# HX6320_SchDoc.net
KiCad netlist of a schematic drawn in Altium Designer
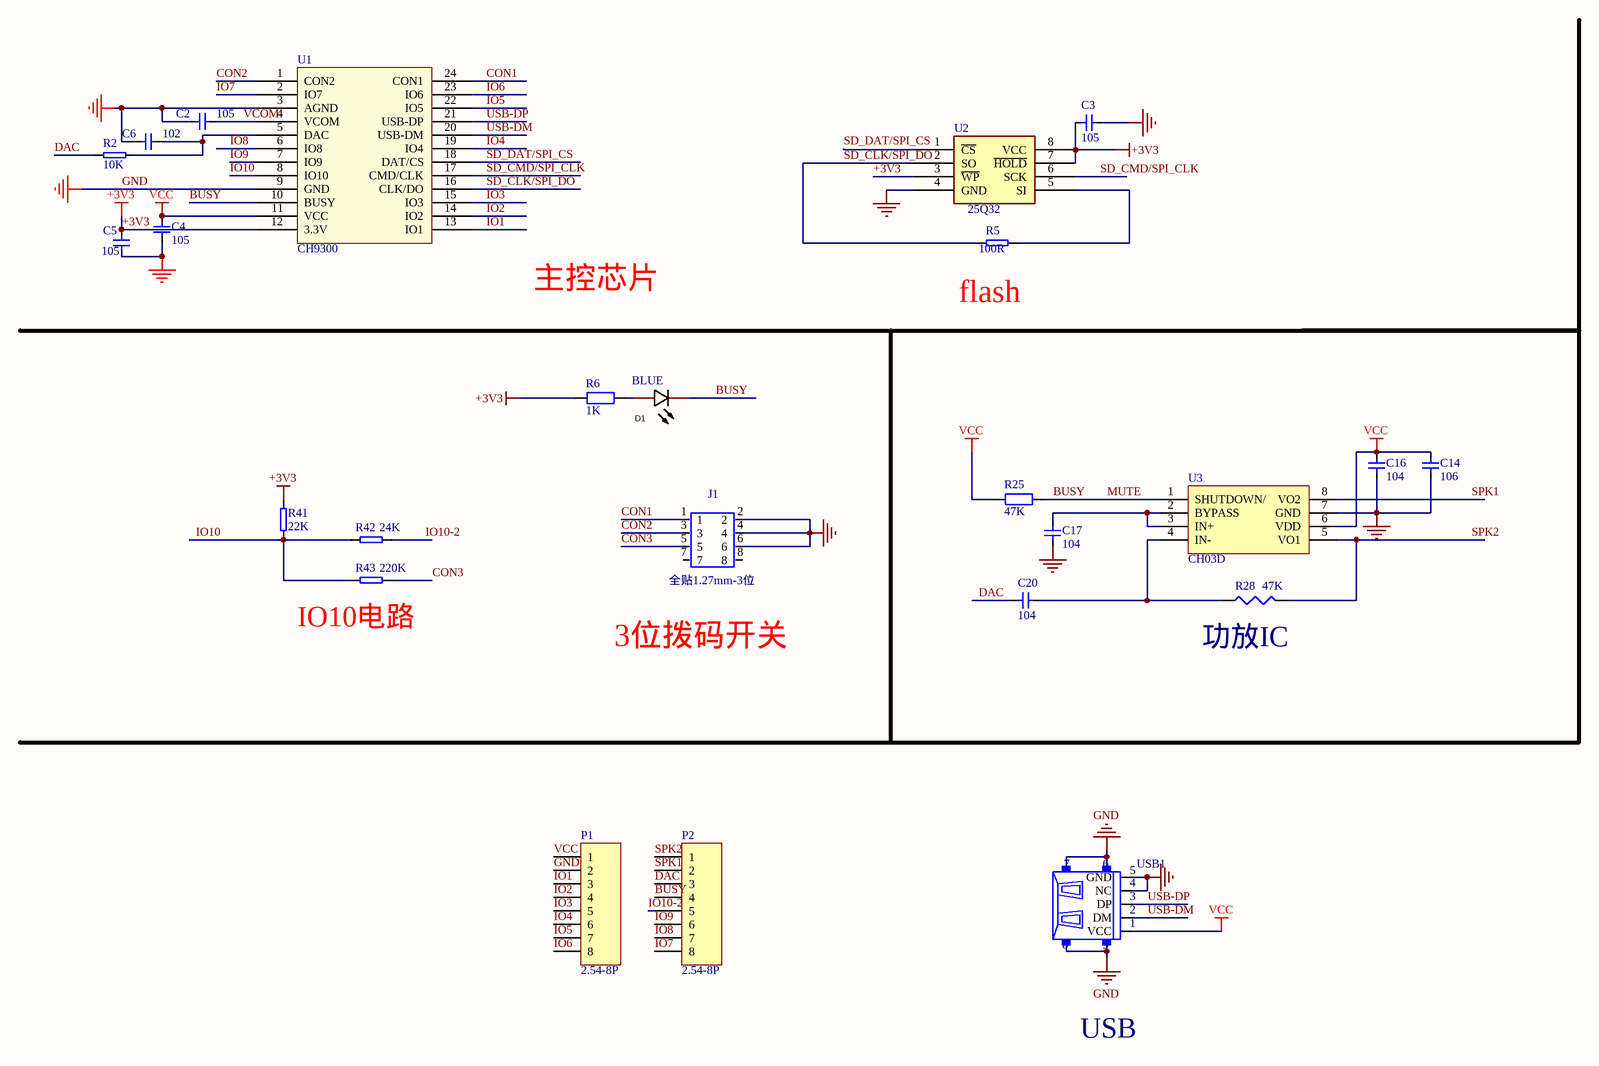
[diagram p0: HX6320.SchDoc.schdoc]

(export (version "E")
  (design (tool "Eeschema 10.0.6"))
  (components
    (comp (ref "C2")
      (value "105")
      (footprint "C0603")
      (description "Capacitor")
      (libsource (lib "*") (part "CAP"))
    )
    (comp (ref "C3")
      (value "105")
      (footprint "C0603")
      (description "Capacitor")
      (libsource (lib "*") (part "CAP"))
    )
    (comp (ref "C4")
      (value "105")
      (footprint "C0603")
      (description "Capacitor")
      (libsource (lib "*") (part "CAP"))
    )
    (comp (ref "C5")
      (value "105")
      (footprint "C0603")
      (description "Capacitor")
      (libsource (lib "*") (part "CAP"))
    )
    (comp (ref "C6")
      (value "102")
      (footprint "C0603")
      (description "Capacitor")
      (libsource (lib "*") (part "CAP"))
    )
    (comp (ref "C14")
      (value "106")
      (footprint "C0603")
      (description "Capacitor")
      (libsource (lib "*") (part "CAP"))
    )
    (comp (ref "C16")
      (value "104")
      (footprint "C0603")
      (description "Capacitor")
      (libsource (lib "*") (part "CAP"))
    )
    (comp (ref "C17")
      (value "104")
      (footprint "C0603")
      (description "Capacitor")
      (libsource (lib "*") (part "CAP"))
    )
    (comp (ref "C20")
      (value "104")
      (footprint "C0603")
      (description "Capacitor")
      (libsource (lib "*") (part "CAP"))
    )
    (comp (ref "D1")
      (value "BLUE")
      (footprint "LC-0603_LED_S1")
      (fields (field (name "MANUFACTURER") "国星光电") (field (name "MANUFACTURER PART") "NCD0603R1"))
      (libsource (lib "altium-import") (part "root_2_NCD0603R1_C84263_"))
    )
    (comp (ref "J1")
      (value "全贴1.27mm-3位")
      (footprint "SW-SMD_DSHP02TSGER")
      (libsource (lib "*") (part "CON_A"))
    )
    (comp (ref "P1")
      (value "2.54-8P")
      (footprint "HDR1X8")
      (description "Header, 8-Pin")
      (fields (field (name "PUBLISHER") "Altium Limited"))
      (libsource (lib "Miscellaneous Connectors") (part "Header 8"))
    )
    (comp (ref "P2")
      (value "2.54-8P")
      (footprint "HDR1X8")
      (description "Header, 8-Pin")
      (fields (field (name "PUBLISHER") "Altium Limited"))
      (libsource (lib "Miscellaneous Connectors") (part "Header 8"))
    )
    (comp (ref "R2") (value "10K") (footprint "R0603") (libsource (lib "*") (part "RES")))
    (comp (ref "R5") (value "100R") (footprint "R0603") (libsource (lib "*") (part "RES")))
    (comp (ref "R6")
      (value "1K")
      (footprint "R0603")
      (description "贴片电阻")
      (fields (field (name "版权归属") "源创客"))
      (libsource (lib "电阻-电容-电感") (part "R"))
    )
    (comp (ref "R25")
      (value "47K")
      (footprint "R0603")
      (description "贴片电阻")
      (fields (field (name "版权归属") "源创客"))
      (libsource (lib "电阻-电容-电感") (part "R"))
    )
    (comp (ref "R28")
      (value "47K")
      (footprint "R0603")
      (description "0805.PcbLib")
      (fields (field (name "PUBLISHER") "Altium Limited"))
      (libsource (lib "*") (part "Res3"))
    )
    (comp (ref "R41") (value "22K") (footprint "R0603") (libsource (lib "*") (part "RES")))
    (comp (ref "R42") (value "24K") (footprint "R0603") (libsource (lib "*") (part "RES")))
    (comp (ref "R43") (value "220K") (footprint "R0603") (libsource (lib "*") (part "RES")))
    (comp (ref "U1") (value "CH9300") (footprint "QSOP24") (libsource (lib "JQ8900") (part "COMPONENT_2")))
    (comp (ref "U2") (value "25Q32") (footprint "LC-SOIC-8_150-208mil") (libsource (lib "*") (part "A25Q32")))
    (comp (ref "U3") (value "CH03D") (footprint "LC-SOP-8_150mil") (libsource (lib "IC") (part "LM4890")))
    (comp (ref "USB1") (value "USB-5PIN") (footprint "USB-MIRO") (libsource (lib "*") (part "USB-5PIN")))
  )
  (nets
    (net (code "1") (name "+3V3") (class "Default")
      (node (ref "C3") (pin "1") (pinfunction "1_1") (pintype "passive"))
      (node (ref "C5") (pin "1") (pinfunction "1_1") (pintype "passive"))
      (node (ref "R41") (pin "2") (pinfunction "2_2") (pintype "passive"))
      (node (ref "R6") (pin "1") (pinfunction "1_1") (pintype "passive"))
      (node (ref "U1") (pin "12") (pinfunction "3.3V_12") (pintype "passive"))
      (node (ref "U2") (pin "3") (pinfunction "~{WP}_3") (pintype "passive"))
      (node (ref "U2") (pin "7") (pinfunction "~{HOLD}_7") (pintype "passive"))
      (node (ref "U2") (pin "8") (pinfunction "VCC_8") (pintype "passive"))
    )
    (net (code "2") (name "/BUSY") (class "Default")
      (node (ref "D1") (pin "1") (pinfunction "K_1") (pintype "passive"))
      (node (ref "P2") (pin "4") (pinfunction "4_4") (pintype "passive"))
      (node (ref "R25") (pin "1") (pinfunction "1_1") (pintype "passive"))
      (node (ref "U1") (pin "10") (pinfunction "BUSY_10") (pintype "passive"))
      (node (ref "U3") (pin "1") (pinfunction "SHUTDOWN/_1") (pintype "passive"))
    )
    (net (code "3") (name "/CON1") (class "Default")
      (node (ref "J1") (pin "1") (pinfunction "1_1") (pintype "passive"))
      (node (ref "U1") (pin "24") (pinfunction "CON1_24") (pintype "passive"))
    )
    (net (code "4") (name "/CON2") (class "Default")
      (node (ref "J1") (pin "3") (pinfunction "3_3") (pintype "passive"))
      (node (ref "U1") (pin "1") (pinfunction "CON2_1") (pintype "passive"))
    )
    (net (code "5") (name "/CON3") (class "Default")
      (node (ref "J1") (pin "5") (pinfunction "5_5") (pintype "passive"))
      (node (ref "R43") (pin "1") (pinfunction "1_1") (pintype "passive"))
    )
    (net (code "6") (name "/DAC") (class "Default")
      (node (ref "C20") (pin "1") (pinfunction "1_1") (pintype "passive"))
      (node (ref "P2") (pin "3") (pinfunction "3_3") (pintype "passive"))
      (node (ref "R2") (pin "2") (pinfunction "2_2") (pintype "passive"))
    )
    (net (code "7") (name "/IO1") (class "Default")
      (node (ref "P1") (pin "3") (pinfunction "3_3") (pintype "passive"))
      (node (ref "U1") (pin "13") (pinfunction "IO1_13") (pintype "passive"))
    )
    (net (code "8") (name "/IO2") (class "Default")
      (node (ref "P1") (pin "4") (pinfunction "4_4") (pintype "passive"))
      (node (ref "U1") (pin "14") (pinfunction "IO2_14") (pintype "passive"))
    )
    (net (code "9") (name "/IO3") (class "Default")
      (node (ref "P1") (pin "5") (pinfunction "5_5") (pintype "passive"))
      (node (ref "U1") (pin "15") (pinfunction "IO3_15") (pintype "passive"))
    )
    (net (code "10") (name "/IO4") (class "Default")
      (node (ref "P1") (pin "6") (pinfunction "6_6") (pintype "passive"))
      (node (ref "U1") (pin "19") (pinfunction "IO4_19") (pintype "passive"))
    )
    (net (code "11") (name "/IO5") (class "Default")
      (node (ref "P1") (pin "7") (pinfunction "7_7") (pintype "passive"))
      (node (ref "U1") (pin "22") (pinfunction "IO5_22") (pintype "passive"))
    )
    (net (code "12") (name "/IO6") (class "Default")
      (node (ref "P1") (pin "8") (pinfunction "8_8") (pintype "passive"))
      (node (ref "U1") (pin "23") (pinfunction "IO6_23") (pintype "passive"))
    )
    (net (code "13") (name "/IO7") (class "Default")
      (node (ref "P2") (pin "8") (pinfunction "8_8") (pintype "passive"))
      (node (ref "U1") (pin "2") (pinfunction "IO7_2") (pintype "passive"))
    )
    (net (code "14") (name "/IO8") (class "Default")
      (node (ref "P2") (pin "7") (pinfunction "7_7") (pintype "passive"))
      (node (ref "U1") (pin "6") (pinfunction "IO8_6") (pintype "passive"))
    )
    (net (code "15") (name "/IO9") (class "Default")
      (node (ref "P2") (pin "6") (pinfunction "6_6") (pintype "passive"))
      (node (ref "U1") (pin "7") (pinfunction "IO9_7") (pintype "passive"))
    )
    (net (code "16") (name "/IO10") (class "Default")
      (node (ref "R41") (pin "1") (pinfunction "1_1") (pintype "passive"))
      (node (ref "R42") (pin "2") (pinfunction "2_2") (pintype "passive"))
      (node (ref "R43") (pin "2") (pinfunction "2_2") (pintype "passive"))
      (node (ref "U1") (pin "8") (pinfunction "IO10_8") (pintype "passive"))
    )
    (net (code "17") (name "/IO10-2") (class "Default")
      (node (ref "P2") (pin "5") (pinfunction "5_5") (pintype "passive"))
      (node (ref "R42") (pin "1") (pinfunction "1_1") (pintype "passive"))
    )
    (net (code "18") (name "/SD_CLK{slash}SPI_DO") (class "Default")
      (node (ref "R5") (pin "2") (pinfunction "2_2") (pintype "passive"))
      (node (ref "U1") (pin "16") (pinfunction "CLK/DO_16") (pintype "passive"))
      (node (ref "U2") (pin "2") (pinfunction "SO_2") (pintype "passive"))
    )
    (net (code "19") (name "/SD_CMD{slash}SPI_CLK") (class "Default")
      (node (ref "U1") (pin "17") (pinfunction "CMD/CLK_17") (pintype "passive"))
      (node (ref "U2") (pin "6") (pinfunction "SCK_6") (pintype "passive"))
    )
    (net (code "20") (name "/SD_DAT{slash}SPI_CS") (class "Default")
      (node (ref "U1") (pin "18") (pinfunction "DAT/CS_18") (pintype "passive"))
      (node (ref "U2") (pin "1") (pinfunction "~{CS}_1") (pintype "passive"))
    )
    (net (code "21") (name "/SPK1") (class "Default")
      (node (ref "P2") (pin "2") (pinfunction "2_2") (pintype "passive"))
      (node (ref "U3") (pin "8") (pinfunction "VO2_8") (pintype "passive"))
    )
    (net (code "22") (name "/SPK2") (class "Default")
      (node (ref "P2") (pin "1") (pinfunction "1_1") (pintype "passive"))
      (node (ref "R28") (pin "2") (pinfunction "2_2") (pintype "passive"))
      (node (ref "U3") (pin "5") (pinfunction "VO1_5") (pintype "passive"))
    )
    (net (code "23") (name "/USB-DM") (class "Default")
      (node (ref "U1") (pin "20") (pinfunction "USB-DM_20") (pintype "passive"))
      (node (ref "USB1") (pin "2") (pinfunction "DM_2") (pintype "passive"))
    )
    (net (code "24") (name "/USB-DP") (class "Default")
      (node (ref "U1") (pin "21") (pinfunction "USB-DP_21") (pintype "passive"))
      (node (ref "USB1") (pin "3") (pinfunction "DP_3") (pintype "passive"))
    )
    (net (code "25") (name "/VCOM") (class "Default")
      (node (ref "C2") (pin "1") (pinfunction "1_1") (pintype "passive"))
      (node (ref "U1") (pin "4") (pinfunction "VCOM_4") (pintype "passive"))
    )
    (net (code "26") (name "GND") (class "Default")
      (node (ref "C14") (pin "1") (pinfunction "1_1") (pintype "passive"))
      (node (ref "C16") (pin "1") (pinfunction "1_1") (pintype "passive"))
      (node (ref "C17") (pin "1") (pinfunction "1_1") (pintype "passive"))
      (node (ref "C2") (pin "2") (pinfunction "2_2") (pintype "passive"))
      (node (ref "C3") (pin "2") (pinfunction "2_2") (pintype "passive"))
      (node (ref "C4") (pin "1") (pinfunction "1_1") (pintype "passive"))
      (node (ref "C5") (pin "2") (pinfunction "2_2") (pintype "passive"))
      (node (ref "C6") (pin "2") (pinfunction "2_2") (pintype "passive"))
      (node (ref "J1") (pin "2") (pinfunction "2_2") (pintype "passive"))
      (node (ref "J1") (pin "4") (pinfunction "4_4") (pintype "passive"))
      (node (ref "J1") (pin "6") (pinfunction "6_6") (pintype "passive"))
      (node (ref "P1") (pin "2") (pinfunction "2_2") (pintype "passive"))
      (node (ref "U1") (pin "3") (pinfunction "AGND_3") (pintype "passive"))
      (node (ref "U1") (pin "9") (pinfunction "GND_9") (pintype "passive"))
      (node (ref "U2") (pin "4") (pinfunction "GND_4") (pintype "passive"))
      (node (ref "U3") (pin "7") (pinfunction "GND_7") (pintype "passive"))
      (node (ref "USB1") (pin "4") (pinfunction "NC_4") (pintype "passive"))
      (node (ref "USB1") (pin "5") (pinfunction "GND_5") (pintype "passive"))
      (node (ref "USB1") (pin "6") (pinfunction "6_6") (pintype "passive"))
      (node (ref "USB1") (pin "7") (pinfunction "7_7") (pintype "passive"))
      (node (ref "USB1") (pin "8") (pinfunction "8_8") (pintype "passive"))
      (node (ref "USB1") (pin "9") (pinfunction "9_9") (pintype "passive"))
    )
    (net (code "27") (name "Net-(D1-A)") (class "Default")
      (node (ref "D1") (pin "2") (pinfunction "A_2") (pintype "passive"))
      (node (ref "R6") (pin "2") (pinfunction "2_2") (pintype "passive"))
    )
    (net (code "28") (name "Net-(U1-DAC)") (class "Default")
      (node (ref "C6") (pin "1") (pinfunction "1_1") (pintype "passive"))
      (node (ref "R2") (pin "1") (pinfunction "1_1") (pintype "passive"))
      (node (ref "U1") (pin "5") (pinfunction "DAC_5") (pintype "passive"))
    )
    (net (code "29") (name "Net-(U2-SI)") (class "Default")
      (node (ref "R5") (pin "1") (pinfunction "1_1") (pintype "passive"))
      (node (ref "U2") (pin "5") (pinfunction "SI_5") (pintype "passive"))
    )
    (net (code "30") (name "Net-(U3-BYPASS)") (class "Default")
      (node (ref "C17") (pin "2") (pinfunction "2_2") (pintype "passive"))
      (node (ref "U3") (pin "2") (pinfunction "BYPASS_2") (pintype "passive"))
      (node (ref "U3") (pin "3") (pinfunction "IN+_3") (pintype "passive"))
    )
    (net (code "31") (name "Net-(U3-IN-)") (class "Default")
      (node (ref "C20") (pin "2") (pinfunction "2_2") (pintype "passive"))
      (node (ref "R28") (pin "1") (pinfunction "1_1") (pintype "passive"))
      (node (ref "U3") (pin "4") (pinfunction "IN-_4") (pintype "passive"))
    )
    (net (code "32") (name "VCC") (class "Default")
      (node (ref "C14") (pin "2") (pinfunction "2_2") (pintype "passive"))
      (node (ref "C16") (pin "2") (pinfunction "2_2") (pintype "passive"))
      (node (ref "C4") (pin "2") (pinfunction "2_2") (pintype "passive"))
      (node (ref "P1") (pin "1") (pinfunction "1_1") (pintype "passive"))
      (node (ref "R25") (pin "2") (pinfunction "2_2") (pintype "passive"))
      (node (ref "U1") (pin "11") (pinfunction "VCC_11") (pintype "passive"))
      (node (ref "U3") (pin "6") (pinfunction "VDD_6") (pintype "passive"))
      (node (ref "USB1") (pin "1") (pinfunction "VCC_1") (pintype "passive"))
    )
    (net (code "33") (name "unconnected-(J1-Pad7)") (class "Default")
      (node (ref "J1") (pin "7") (pinfunction "7_7") (pintype "passive"))
    )
    (net (code "34") (name "unconnected-(J1-Pad8)") (class "Default")
      (node (ref "J1") (pin "8") (pinfunction "8_8") (pintype "passive"))
    )
  )
)
